# mainboard.net
KiCad netlist of a schematic drawn in EAGLE
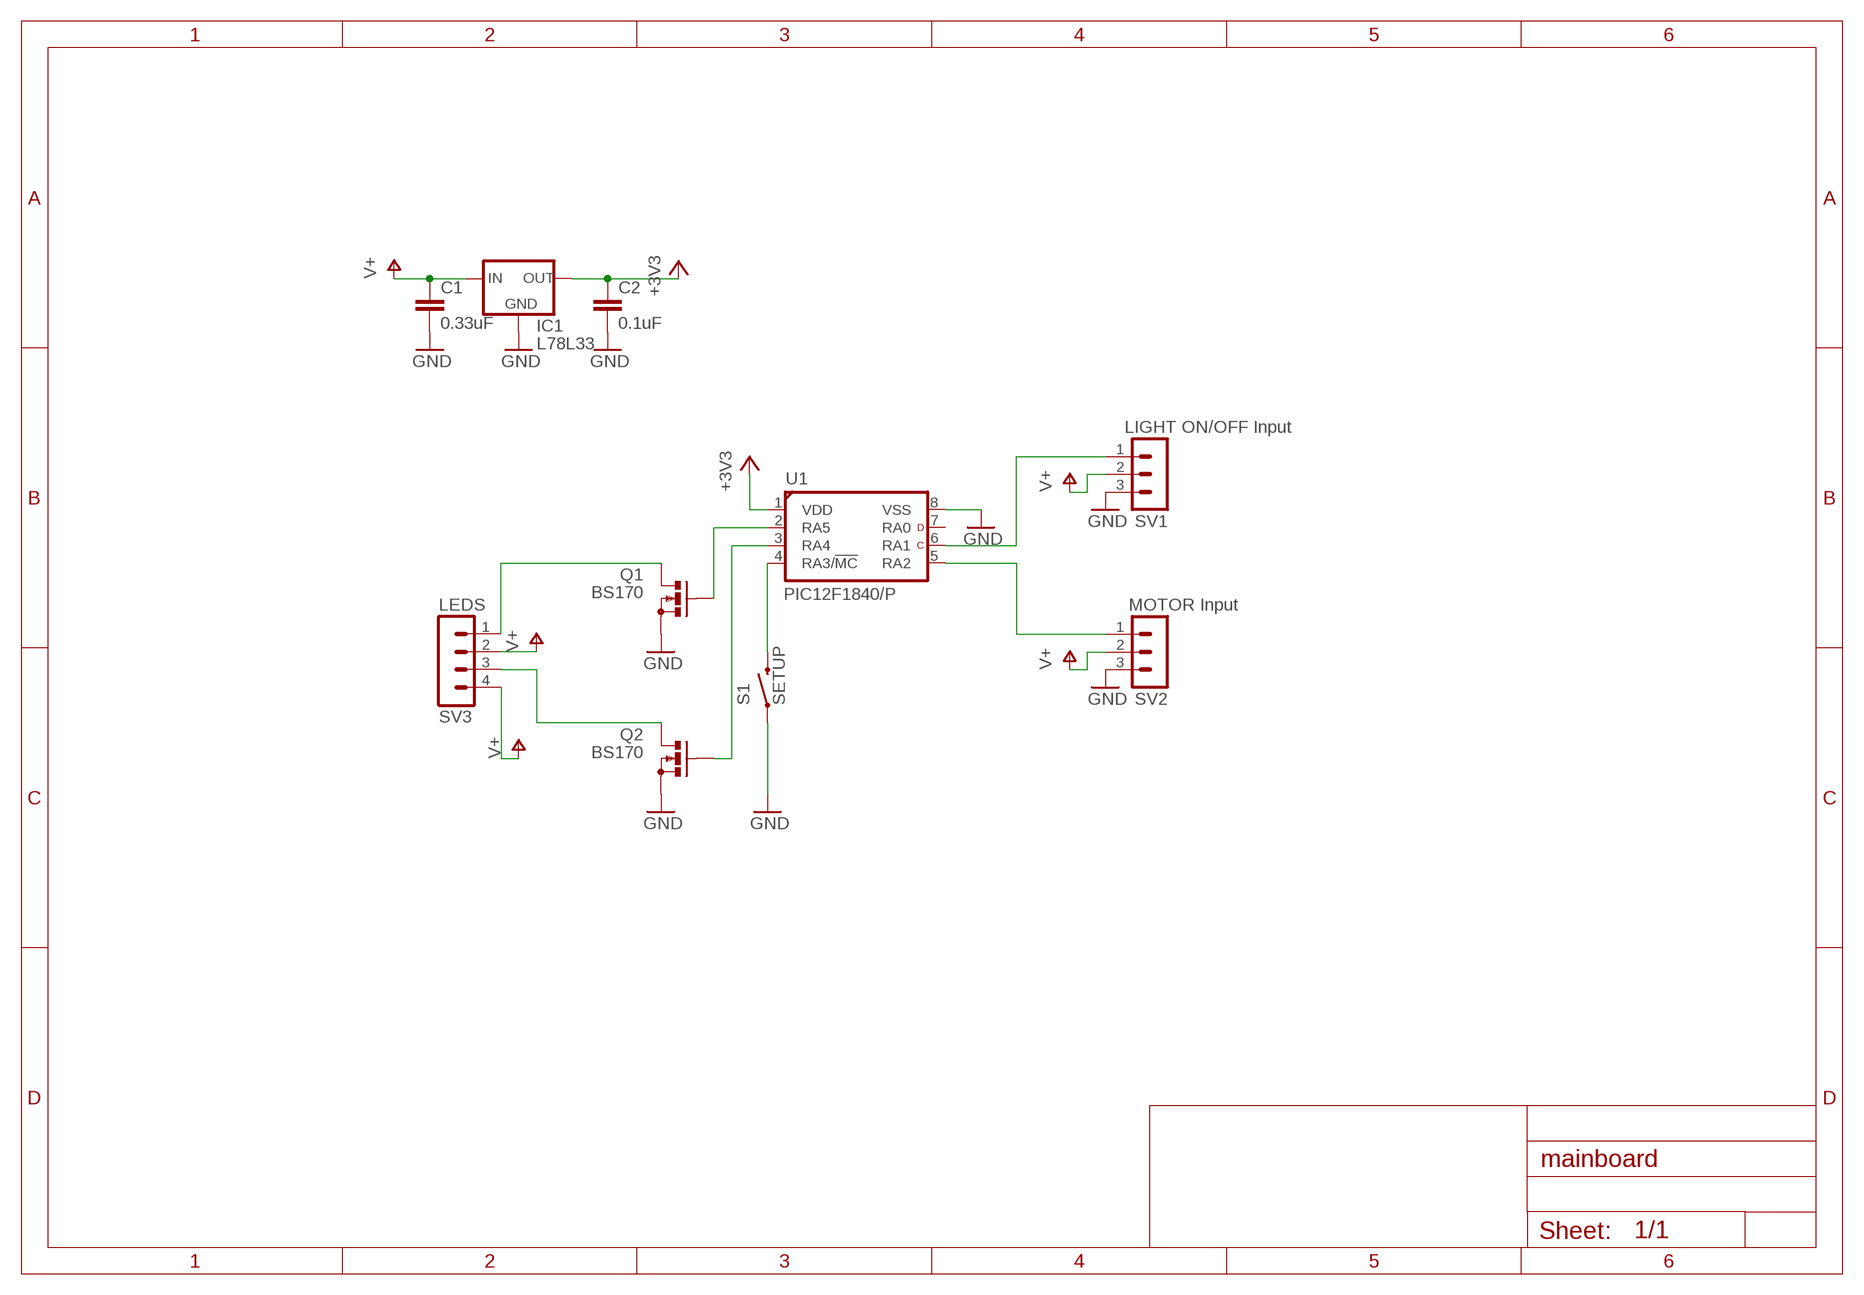
[diagram p0: schematic, sheet 1]

(export (version "E")
  (design (tool "Eeschema 10.0.6"))
  (components
    (comp (ref "C1")
      (value "0.33uF")
      (footprint "eagle-import:C025-025X050")
      (libsource (lib "eagle-import") (part "C-EU025-025X050"))
    )
    (comp (ref "C2")
      (value "0.1uF")
      (footprint "eagle-import:C025-025X050")
      (libsource (lib "eagle-import") (part "C-EU025-025X050"))
    )
    (comp (ref "IC1")
      (value "L78L33")
      (footprint "eagle-import:78LXX")
      (libsource (lib "eagle-import") (part "78LXX"))
    )
    (comp (ref "Q1")
      (value "BS170")
      (footprint "eagle-import:SOT54E")
      (libsource (lib "eagle-import") (part "BS170"))
    )
    (comp (ref "Q2")
      (value "BS170")
      (footprint "eagle-import:SOT54E")
      (libsource (lib "eagle-import") (part "BS170"))
    )
    (comp (ref "S1")
      (value "SETUP")
      (footprint "eagle-import:TACTILE-PTH")
      (libsource (lib "eagle-import") (part "SWITCH-MOMENTARY-2PTH"))
    )
    (comp (ref "SV1")
      (value "LIGHT ON/OFF Input")
      (footprint "eagle-import:MA03-1")
      (libsource (lib "eagle-import") (part "MA03-1"))
    )
    (comp (ref "SV2")
      (value "MOTOR Input")
      (footprint "eagle-import:MA03-1")
      (libsource (lib "eagle-import") (part "MA03-1"))
    )
    (comp (ref "SV3")
      (value "LEDS")
      (footprint "eagle-import:MA04-1")
      (libsource (lib "eagle-import") (part "MA04-1"))
    )
    (comp (ref "U1")
      (value "PIC12F1840/P")
      (footprint "eagle-import:DIL8-P")
      (libsource (lib "eagle-import") (part "PIC12F1840/P"))
    )
  )
  (nets
    (net (code "1") (name "+3V3") (class "Default")
      (node (ref "C2") (pin "1") (pinfunction "1_1") (pintype "passive"))
      (node (ref "IC1") (pin "OUT") (pinfunction "OUT_OUT") (pintype "passive"))
      (node (ref "U1") (pin "1") (pinfunction "VDD_1") (pintype "passive"))
    )
    (net (code "2") (name "GND") (class "Default")
      (node (ref "C1") (pin "2") (pinfunction "2_2") (pintype "passive"))
      (node (ref "C2") (pin "2") (pinfunction "2_2") (pintype "passive"))
      (node (ref "IC1") (pin "GND") (pinfunction "GND_GND") (pintype "input"))
      (node (ref "Q1") (pin "S") (pinfunction "S_S") (pintype "passive"))
      (node (ref "Q2") (pin "S") (pinfunction "S_S") (pintype "passive"))
      (node (ref "S1") (pin "1") (pinfunction "1_1") (pintype "passive"))
      (node (ref "SV1") (pin "3") (pinfunction "3_3") (pintype "passive"))
      (node (ref "SV2") (pin "3") (pinfunction "3_3") (pintype "passive"))
      (node (ref "U1") (pin "8") (pinfunction "VSS_8") (pintype "passive"))
    )
    (net (code "3") (name "Net-(Q1-PadD)") (class "Default")
      (node (ref "Q1") (pin "D") (pinfunction "D_D") (pintype "passive"))
      (node (ref "SV3") (pin "1") (pinfunction "1_1") (pintype "passive"))
    )
    (net (code "4") (name "Net-(Q2-PadD)") (class "Default")
      (node (ref "Q2") (pin "D") (pinfunction "D_D") (pintype "passive"))
      (node (ref "SV3") (pin "3") (pinfunction "3_3") (pintype "passive"))
    )
    (net (code "5") (name "Net-(S1-2)") (class "Default")
      (node (ref "S1") (pin "3") (pinfunction "2_3") (pintype "passive"))
      (node (ref "U1") (pin "4") (pinfunction "RA3/~{MC}_4") (pintype "bidirectional"))
    )
    (net (code "6") (name "Net-(U1-RA1)") (class "Default")
      (node (ref "SV1") (pin "1") (pinfunction "1_1") (pintype "passive"))
      (node (ref "U1") (pin "6") (pinfunction "RA1_6") (pintype "bidirectional"))
    )
    (net (code "7") (name "Net-(U1-RA2)") (class "Default")
      (node (ref "SV2") (pin "1") (pinfunction "1_1") (pintype "passive"))
      (node (ref "U1") (pin "5") (pinfunction "RA2_5") (pintype "bidirectional"))
    )
    (net (code "8") (name "Net-(U1-RA4)") (class "Default")
      (node (ref "Q2") (pin "G") (pinfunction "G_G") (pintype "passive"))
      (node (ref "U1") (pin "3") (pinfunction "RA4_3") (pintype "bidirectional"))
    )
    (net (code "9") (name "Net-(U1-RA5)") (class "Default")
      (node (ref "Q1") (pin "G") (pinfunction "G_G") (pintype "passive"))
      (node (ref "U1") (pin "2") (pinfunction "RA5_2") (pintype "bidirectional"))
    )
    (net (code "10") (name "V+") (class "Default")
      (node (ref "C1") (pin "1") (pinfunction "1_1") (pintype "passive"))
      (node (ref "IC1") (pin "IN") (pinfunction "IN_IN") (pintype "input"))
      (node (ref "SV1") (pin "2") (pinfunction "2_2") (pintype "passive"))
      (node (ref "SV2") (pin "2") (pinfunction "2_2") (pintype "passive"))
      (node (ref "SV3") (pin "2") (pinfunction "2_2") (pintype "passive"))
      (node (ref "SV3") (pin "4") (pinfunction "4_4") (pintype "passive"))
    )
    (net (code "11") (name "unconnected-(U1-RA0-Pad7)") (class "Default")
      (node (ref "U1") (pin "7") (pinfunction "RA0_7") (pintype "bidirectional"))
    )
  )
)
